# VIC20_HypExp.net
KiCad netlist of a schematic drawn in EAGLE
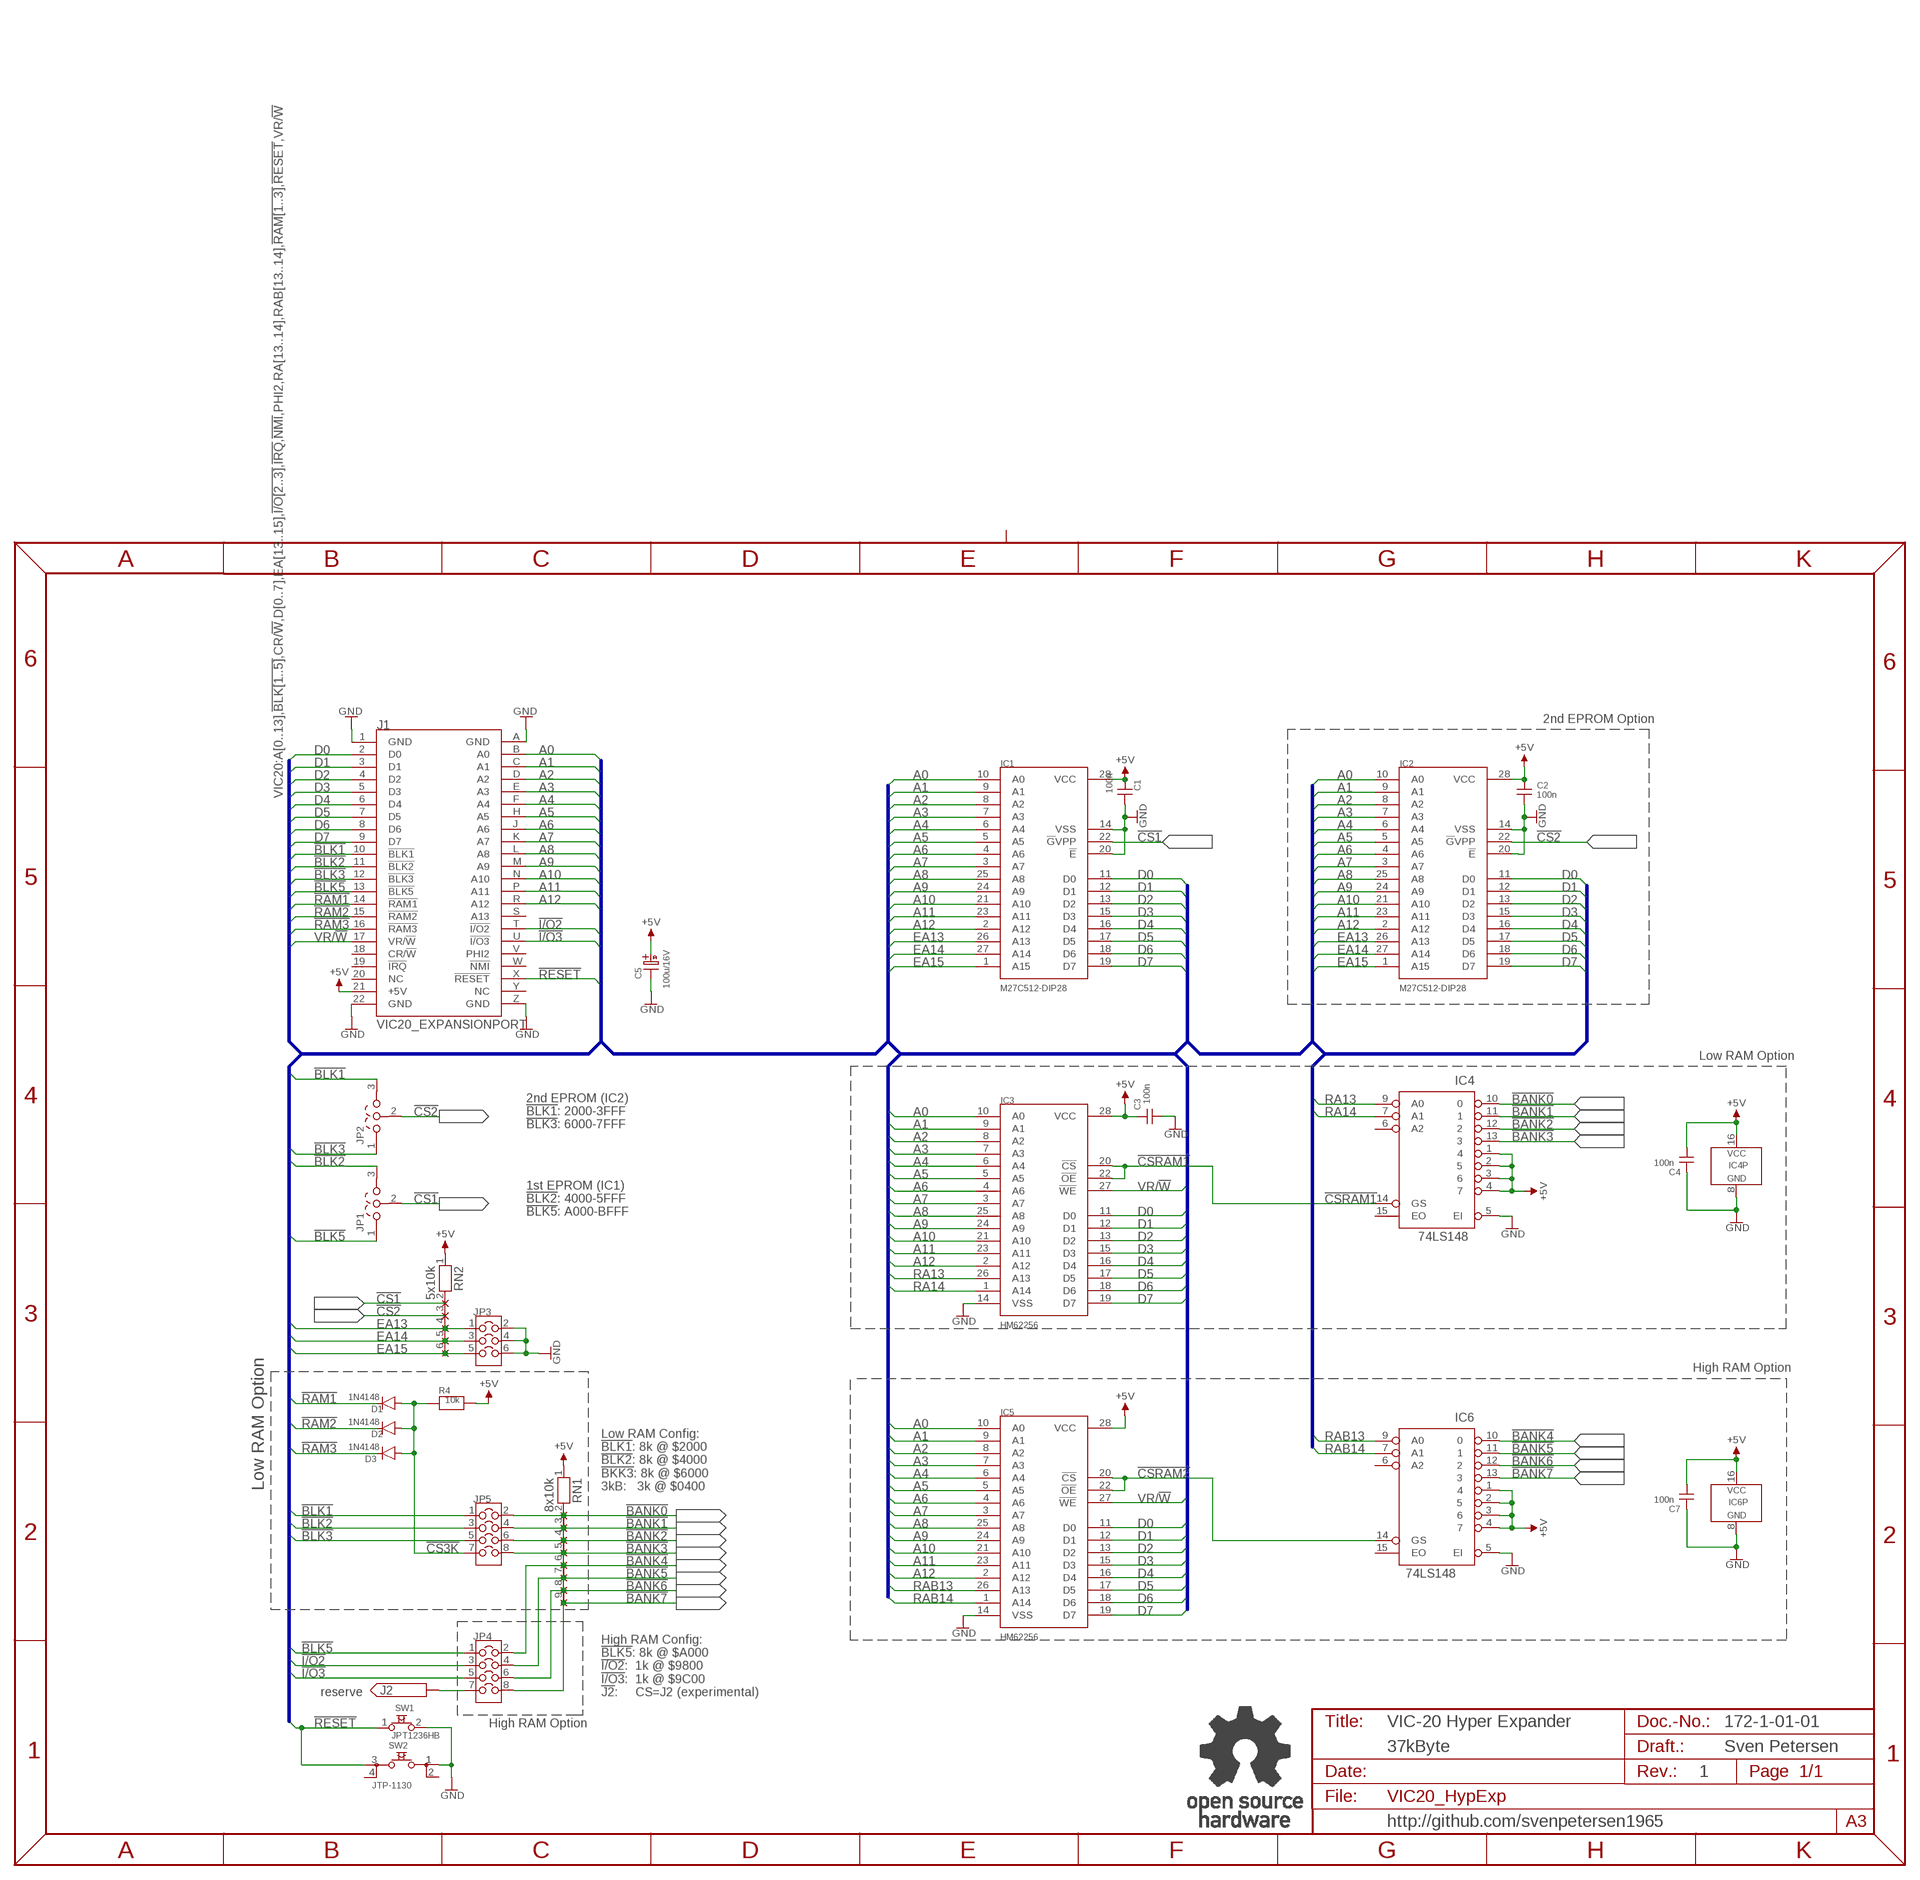
[diagram p0: schematic, sheet 1]

(export (version "E")
  (design (tool "Eeschema 10.0.6"))
  (components
    (comp (ref "C1")
      (value "100n")
      (footprint "eagle-import:C-2,5")
      (libsource (lib "eagle-import") (part "CAP01"))
    )
    (comp (ref "C2")
      (value "100n")
      (footprint "eagle-import:C-2,5")
      (libsource (lib "eagle-import") (part "CAP01"))
    )
    (comp (ref "C3")
      (value "100n")
      (footprint "eagle-import:C-2,5")
      (libsource (lib "eagle-import") (part "CAP01"))
    )
    (comp (ref "C4")
      (value "100n")
      (footprint "eagle-import:C-2,5")
      (libsource (lib "eagle-import") (part "CAP01"))
    )
    (comp (ref "C5")
      (value "100u/16V")
      (footprint "eagle-import:C07_2,5")
      (libsource (lib "eagle-import") (part "C07/2,5"))
    )
    (comp (ref "C7")
      (value "100n")
      (footprint "eagle-import:C-2,5")
      (libsource (lib "eagle-import") (part "CAP01"))
    )
    (comp (ref "D1")
      (value "1N4148")
      (footprint "eagle-import:DO-35_3")
      (libsource (lib "eagle-import") (part "1N41480.3{dblquote}"))
    )
    (comp (ref "D2")
      (value "1N4148")
      (footprint "eagle-import:DO-35_3")
      (libsource (lib "eagle-import") (part "1N41480.3{dblquote}"))
    )
    (comp (ref "D3")
      (value "1N4148")
      (footprint "eagle-import:DO-35_3")
      (libsource (lib "eagle-import") (part "1N41480.3{dblquote}"))
    )
    (comp (ref "IC1")
      (value "M27C512-DIP28")
      (footprint "eagle-import:DIL28-6")
      (libsource (lib "eagle-import") (part "M27C512-DIP28"))
    )
    (comp (ref "IC2")
      (value "M27C512-DIP28")
      (footprint "eagle-import:DIL28-6")
      (libsource (lib "eagle-import") (part "M27C512-DIP28"))
    )
    (comp (ref "IC3")
      (value "HM62256")
      (footprint "eagle-import:DIL28-6")
      (libsource (lib "eagle-import") (part "HM62256"))
    )
    (comp (ref "IC4")
      (value "74LS148")
      (footprint "eagle-import:DIL-16")
      (libsource (lib "eagle-import") (part "74148DIL"))
    )
    (comp (ref "IC5")
      (value "HM62256")
      (footprint "eagle-import:DIL28-6")
      (libsource (lib "eagle-import") (part "HM62256"))
    )
    (comp (ref "IC6")
      (value "74LS148")
      (footprint "eagle-import:DIL-16")
      (libsource (lib "eagle-import") (part "74148DIL"))
    )
    (comp (ref "J1")
      (value "VIC20_EXPANSIONPORT")
      (footprint "eagle-import:VIC20_EXPANSION")
      (libsource (lib "eagle-import") (part "VIC20_EXPANSIONPORT"))
    )
    (comp (ref "J2")
      (value "PINHD-1X1")
      (footprint "eagle-import:1X01")
      (libsource (lib "eagle-import") (part "PINHD-1X1"))
    )
    (comp (ref "JP1")
      (value "COMBI-3P")
      (footprint "eagle-import:COMBI-3P")
      (libsource (lib "eagle-import") (part "COMBI-3P"))
    )
    (comp (ref "JP2")
      (value "COMBI-3P")
      (footprint "eagle-import:COMBI-3P")
      (libsource (lib "eagle-import") (part "COMBI-3P"))
    )
    (comp (ref "JP3")
      (value "COMBI-3X2P")
      (footprint "eagle-import:COMBI-3X2")
      (libsource (lib "eagle-import") (part "COMBI-3X2P"))
    )
    (comp (ref "JP4")
      (value "COMBI-4X2P")
      (footprint "eagle-import:COMBI-4X2")
      (libsource (lib "eagle-import") (part "COMBI-4X2P"))
    )
    (comp (ref "JP5")
      (value "COMBI-4X2P")
      (footprint "eagle-import:COMBI-4X2")
      (libsource (lib "eagle-import") (part "COMBI-4X2P"))
    )
    (comp (ref "R4")
      (value "10k")
      (footprint "eagle-import:R-10")
      (libsource (lib "eagle-import") (part "RES04"))
    )
    (comp (ref "RN1")
      (value "8x10k")
      (footprint "eagle-import:RN-9")
      (libsource (lib "eagle-import") (part "RN08"))
    )
    (comp (ref "RN2")
      (value "5x10k")
      (footprint "eagle-import:RN-6")
      (libsource (lib "eagle-import") (part "RN05"))
    )
    (comp (ref "SW1")
      (value "JPT1236HB")
      (footprint "eagle-import:JTP_1236HB")
      (libsource (lib "eagle-import") (part "JPT1236HB"))
    )
    (comp (ref "SW2")
      (value "JTP-1130")
      (footprint "eagle-import:JTP-1130")
      (libsource (lib "eagle-import") (part "JTP-1130"))
    )
    (comp (ref "U$2")
      (value "OPEN_SOURCE_HW")
      (footprint "eagle-import:OPENHW")
      (libsource (lib "eagle-import") (part "OPEN_SOURCE_HW"))
    )
  )
  (nets
    (net (code "5") (name "+5V") (class "Default")
      (node (ref "C1") (pin "1") (pinfunction "1_1") (pintype "passive"))
      (node (ref "C2") (pin "1") (pinfunction "1_1") (pintype "passive"))
      (node (ref "C3") (pin "2") (pinfunction "2_2") (pintype "passive"))
      (node (ref "C4") (pin "1") (pinfunction "1_1") (pintype "passive"))
      (node (ref "C5") (pin "A") (pinfunction "+_A") (pintype "passive"))
      (node (ref "C7") (pin "1") (pinfunction "1_1") (pintype "passive"))
      (node (ref "IC1") (pin "28") (pinfunction "VCC_28") (pintype "power_in"))
      (node (ref "IC2") (pin "28") (pinfunction "VCC_28") (pintype "power_in"))
      (node (ref "IC3") (pin "28") (pinfunction "VCC_28") (pintype "power_in"))
      (node (ref "IC4") (pin "1") (pinfunction "4_1") (pintype "input"))
      (node (ref "IC4") (pin "16") (pinfunction "VCC_16") (pintype "bidirectional"))
      (node (ref "IC4") (pin "2") (pinfunction "5_2") (pintype "input"))
      (node (ref "IC4") (pin "3") (pinfunction "6_3") (pintype "input"))
      (node (ref "IC4") (pin "4") (pinfunction "7_4") (pintype "input"))
      (node (ref "IC5") (pin "28") (pinfunction "VCC_28") (pintype "power_in"))
      (node (ref "IC6") (pin "1") (pinfunction "4_1") (pintype "input"))
      (node (ref "IC6") (pin "16") (pinfunction "VCC_16") (pintype "bidirectional"))
      (node (ref "IC6") (pin "2") (pinfunction "5_2") (pintype "input"))
      (node (ref "IC6") (pin "3") (pinfunction "6_3") (pintype "input"))
      (node (ref "IC6") (pin "4") (pinfunction "7_4") (pintype "input"))
      (node (ref "J1") (pin "21") (pinfunction "+5V_21") (pintype "power_in"))
      (node (ref "R4") (pin "2") (pinfunction "2_2") (pintype "passive"))
      (node (ref "RN1") (pin "1") (pinfunction "1_1") (pintype "passive"))
      (node (ref "RN2") (pin "1") (pinfunction "1_1") (pintype "passive"))
    )
    (net (code "6") (name "/A0") (class "Default")
      (node (ref "IC1") (pin "10") (pinfunction "A0_10") (pintype "input"))
      (node (ref "IC2") (pin "10") (pinfunction "A0_10") (pintype "input"))
      (node (ref "IC3") (pin "10") (pinfunction "A0_10") (pintype "input"))
      (node (ref "IC5") (pin "10") (pinfunction "A0_10") (pintype "input"))
      (node (ref "J1") (pin "B") (pinfunction "A0_B") (pintype "bidirectional"))
    )
    (net (code "7") (name "/A1") (class "Default")
      (node (ref "IC1") (pin "9") (pinfunction "A1_9") (pintype "input"))
      (node (ref "IC2") (pin "9") (pinfunction "A1_9") (pintype "input"))
      (node (ref "IC3") (pin "9") (pinfunction "A1_9") (pintype "input"))
      (node (ref "IC5") (pin "9") (pinfunction "A1_9") (pintype "input"))
      (node (ref "J1") (pin "C") (pinfunction "A1_C") (pintype "bidirectional"))
    )
    (net (code "8") (name "/A2") (class "Default")
      (node (ref "IC1") (pin "8") (pinfunction "A2_8") (pintype "input"))
      (node (ref "IC2") (pin "8") (pinfunction "A2_8") (pintype "input"))
      (node (ref "IC3") (pin "8") (pinfunction "A2_8") (pintype "input"))
      (node (ref "IC5") (pin "8") (pinfunction "A2_8") (pintype "input"))
      (node (ref "J1") (pin "D") (pinfunction "A2_D") (pintype "bidirectional"))
    )
    (net (code "9") (name "/A3") (class "Default")
      (node (ref "IC1") (pin "7") (pinfunction "A3_7") (pintype "input"))
      (node (ref "IC2") (pin "7") (pinfunction "A3_7") (pintype "input"))
      (node (ref "IC3") (pin "7") (pinfunction "A3_7") (pintype "input"))
      (node (ref "IC5") (pin "7") (pinfunction "A3_7") (pintype "input"))
      (node (ref "J1") (pin "E") (pinfunction "A3_E") (pintype "bidirectional"))
    )
    (net (code "10") (name "/A4") (class "Default")
      (node (ref "IC1") (pin "6") (pinfunction "A4_6") (pintype "input"))
      (node (ref "IC2") (pin "6") (pinfunction "A4_6") (pintype "input"))
      (node (ref "IC3") (pin "6") (pinfunction "A4_6") (pintype "input"))
      (node (ref "IC5") (pin "6") (pinfunction "A4_6") (pintype "input"))
      (node (ref "J1") (pin "F") (pinfunction "A4_F") (pintype "bidirectional"))
    )
    (net (code "11") (name "/A5") (class "Default")
      (node (ref "IC1") (pin "5") (pinfunction "A5_5") (pintype "input"))
      (node (ref "IC2") (pin "5") (pinfunction "A5_5") (pintype "input"))
      (node (ref "IC3") (pin "5") (pinfunction "A5_5") (pintype "input"))
      (node (ref "IC5") (pin "5") (pinfunction "A5_5") (pintype "input"))
      (node (ref "J1") (pin "H") (pinfunction "A5_H") (pintype "bidirectional"))
    )
    (net (code "12") (name "/A6") (class "Default")
      (node (ref "IC1") (pin "4") (pinfunction "A6_4") (pintype "input"))
      (node (ref "IC2") (pin "4") (pinfunction "A6_4") (pintype "input"))
      (node (ref "IC3") (pin "4") (pinfunction "A6_4") (pintype "input"))
      (node (ref "IC5") (pin "4") (pinfunction "A6_4") (pintype "input"))
      (node (ref "J1") (pin "J") (pinfunction "A6_J") (pintype "bidirectional"))
    )
    (net (code "13") (name "/A7") (class "Default")
      (node (ref "IC1") (pin "3") (pinfunction "A7_3") (pintype "input"))
      (node (ref "IC2") (pin "3") (pinfunction "A7_3") (pintype "input"))
      (node (ref "IC3") (pin "3") (pinfunction "A7_3") (pintype "input"))
      (node (ref "IC5") (pin "3") (pinfunction "A7_3") (pintype "input"))
      (node (ref "J1") (pin "K") (pinfunction "A7_K") (pintype "bidirectional"))
    )
    (net (code "14") (name "/A8") (class "Default")
      (node (ref "IC1") (pin "25") (pinfunction "A8_25") (pintype "input"))
      (node (ref "IC2") (pin "25") (pinfunction "A8_25") (pintype "input"))
      (node (ref "IC3") (pin "25") (pinfunction "A8_25") (pintype "input"))
      (node (ref "IC5") (pin "25") (pinfunction "A8_25") (pintype "input"))
      (node (ref "J1") (pin "L") (pinfunction "A8_L") (pintype "bidirectional"))
    )
    (net (code "15") (name "/A9") (class "Default")
      (node (ref "IC1") (pin "24") (pinfunction "A9_24") (pintype "input"))
      (node (ref "IC2") (pin "24") (pinfunction "A9_24") (pintype "input"))
      (node (ref "IC3") (pin "24") (pinfunction "A9_24") (pintype "input"))
      (node (ref "IC5") (pin "24") (pinfunction "A9_24") (pintype "input"))
      (node (ref "J1") (pin "M") (pinfunction "A9_M") (pintype "bidirectional"))
    )
    (net (code "16") (name "/A10") (class "Default")
      (node (ref "IC1") (pin "21") (pinfunction "A10_21") (pintype "input"))
      (node (ref "IC2") (pin "21") (pinfunction "A10_21") (pintype "input"))
      (node (ref "IC3") (pin "21") (pinfunction "A10_21") (pintype "input"))
      (node (ref "IC5") (pin "21") (pinfunction "A10_21") (pintype "input"))
      (node (ref "J1") (pin "N") (pinfunction "A10_N") (pintype "bidirectional"))
    )
    (net (code "17") (name "/A11") (class "Default")
      (node (ref "IC1") (pin "23") (pinfunction "A11_23") (pintype "input"))
      (node (ref "IC2") (pin "23") (pinfunction "A11_23") (pintype "input"))
      (node (ref "IC3") (pin "23") (pinfunction "A11_23") (pintype "input"))
      (node (ref "IC5") (pin "23") (pinfunction "A11_23") (pintype "input"))
      (node (ref "J1") (pin "P") (pinfunction "A11_P") (pintype "bidirectional"))
    )
    (net (code "18") (name "/A12") (class "Default")
      (node (ref "IC1") (pin "2") (pinfunction "A12_2") (pintype "input"))
      (node (ref "IC2") (pin "2") (pinfunction "A12_2") (pintype "input"))
      (node (ref "IC3") (pin "2") (pinfunction "A12_2") (pintype "input"))
      (node (ref "IC5") (pin "2") (pinfunction "A12_2") (pintype "input"))
      (node (ref "J1") (pin "R") (pinfunction "A12_R") (pintype "bidirectional"))
    )
    (net (code "19") (name "/D0") (class "Default")
      (node (ref "IC1") (pin "11") (pinfunction "D0_11") (pintype "bidirectional"))
      (node (ref "IC2") (pin "11") (pinfunction "D0_11") (pintype "bidirectional"))
      (node (ref "IC3") (pin "11") (pinfunction "D0_11") (pintype "bidirectional"))
      (node (ref "IC5") (pin "11") (pinfunction "D0_11") (pintype "bidirectional"))
      (node (ref "J1") (pin "2") (pinfunction "D0_2") (pintype "bidirectional"))
    )
    (net (code "20") (name "/D1") (class "Default")
      (node (ref "IC1") (pin "12") (pinfunction "D1_12") (pintype "bidirectional"))
      (node (ref "IC2") (pin "12") (pinfunction "D1_12") (pintype "bidirectional"))
      (node (ref "IC3") (pin "12") (pinfunction "D1_12") (pintype "bidirectional"))
      (node (ref "IC5") (pin "12") (pinfunction "D1_12") (pintype "bidirectional"))
      (node (ref "J1") (pin "3") (pinfunction "D1_3") (pintype "bidirectional"))
    )
    (net (code "21") (name "/D2") (class "Default")
      (node (ref "IC1") (pin "13") (pinfunction "D2_13") (pintype "bidirectional"))
      (node (ref "IC2") (pin "13") (pinfunction "D2_13") (pintype "bidirectional"))
      (node (ref "IC3") (pin "13") (pinfunction "D2_13") (pintype "bidirectional"))
      (node (ref "IC5") (pin "13") (pinfunction "D2_13") (pintype "bidirectional"))
      (node (ref "J1") (pin "4") (pinfunction "D2_4") (pintype "bidirectional"))
    )
    (net (code "22") (name "/D3") (class "Default")
      (node (ref "IC1") (pin "15") (pinfunction "D3_15") (pintype "bidirectional"))
      (node (ref "IC2") (pin "15") (pinfunction "D3_15") (pintype "bidirectional"))
      (node (ref "IC3") (pin "15") (pinfunction "D3_15") (pintype "bidirectional"))
      (node (ref "IC5") (pin "15") (pinfunction "D3_15") (pintype "bidirectional"))
      (node (ref "J1") (pin "5") (pinfunction "D3_5") (pintype "bidirectional"))
    )
    (net (code "23") (name "/D4") (class "Default")
      (node (ref "IC1") (pin "16") (pinfunction "D4_16") (pintype "bidirectional"))
      (node (ref "IC2") (pin "16") (pinfunction "D4_16") (pintype "bidirectional"))
      (node (ref "IC3") (pin "16") (pinfunction "D4_16") (pintype "bidirectional"))
      (node (ref "IC5") (pin "16") (pinfunction "D4_16") (pintype "bidirectional"))
      (node (ref "J1") (pin "6") (pinfunction "D4_6") (pintype "bidirectional"))
    )
    (net (code "24") (name "/D5") (class "Default")
      (node (ref "IC1") (pin "17") (pinfunction "D5_17") (pintype "bidirectional"))
      (node (ref "IC2") (pin "17") (pinfunction "D5_17") (pintype "bidirectional"))
      (node (ref "IC3") (pin "17") (pinfunction "D5_17") (pintype "bidirectional"))
      (node (ref "IC5") (pin "17") (pinfunction "D5_17") (pintype "bidirectional"))
      (node (ref "J1") (pin "7") (pinfunction "D5_7") (pintype "bidirectional"))
    )
    (net (code "25") (name "/D6") (class "Default")
      (node (ref "IC1") (pin "18") (pinfunction "D6_18") (pintype "bidirectional"))
      (node (ref "IC2") (pin "18") (pinfunction "D6_18") (pintype "bidirectional"))
      (node (ref "IC3") (pin "18") (pinfunction "D6_18") (pintype "bidirectional"))
      (node (ref "IC5") (pin "18") (pinfunction "D6_18") (pintype "bidirectional"))
      (node (ref "J1") (pin "8") (pinfunction "D6_8") (pintype "bidirectional"))
    )
    (net (code "26") (name "/D7") (class "Default")
      (node (ref "IC1") (pin "19") (pinfunction "D7_19") (pintype "bidirectional"))
      (node (ref "IC2") (pin "19") (pinfunction "D7_19") (pintype "bidirectional"))
      (node (ref "IC3") (pin "19") (pinfunction "D7_19") (pintype "bidirectional"))
      (node (ref "IC5") (pin "19") (pinfunction "D7_19") (pintype "bidirectional"))
      (node (ref "J1") (pin "9") (pinfunction "D7_9") (pintype "bidirectional"))
    )
    (net (code "27") (name "/EA13") (class "Default")
      (node (ref "IC1") (pin "26") (pinfunction "A13_26") (pintype "input"))
      (node (ref "IC2") (pin "26") (pinfunction "A13_26") (pintype "input"))
      (node (ref "JP3") (pin "1") (pinfunction "1_1") (pintype "bidirectional"))
      (node (ref "RN2") (pin "4") (pinfunction "4_4") (pintype "passive"))
    )
    (net (code "28") (name "/EA14") (class "Default")
      (node (ref "IC1") (pin "27") (pinfunction "A14_27") (pintype "input"))
      (node (ref "IC2") (pin "27") (pinfunction "A14_27") (pintype "input"))
      (node (ref "JP3") (pin "3") (pinfunction "3_3") (pintype "bidirectional"))
      (node (ref "RN2") (pin "5") (pinfunction "5_5") (pintype "passive"))
    )
    (net (code "29") (name "/EA15") (class "Default")
      (node (ref "IC1") (pin "1") (pinfunction "A15_1") (pintype "input"))
      (node (ref "IC2") (pin "1") (pinfunction "A15_1") (pintype "input"))
      (node (ref "JP3") (pin "5") (pinfunction "5_5") (pintype "bidirectional"))
      (node (ref "RN2") (pin "6") (pinfunction "6_6") (pintype "passive"))
    )
    (net (code "30") (name "/NC") (class "Default")
      (node (ref "J1") (pin "20") (pinfunction "NC_20") (pintype "power_in"))
    )
    (net (code "31") (name "/RA13") (class "Default")
      (node (ref "IC3") (pin "26") (pinfunction "A13_26") (pintype "input"))
      (node (ref "IC4") (pin "9") (pinfunction "A0_9") (pintype "output"))
    )
    (net (code "32") (name "/RA14") (class "Default")
      (node (ref "IC3") (pin "1") (pinfunction "A14_1") (pintype "input"))
      (node (ref "IC4") (pin "7") (pinfunction "A1_7") (pintype "output"))
    )
    (net (code "33") (name "/RAB13") (class "Default")
      (node (ref "IC5") (pin "26") (pinfunction "A13_26") (pintype "input"))
      (node (ref "IC6") (pin "9") (pinfunction "A0_9") (pintype "output"))
    )
    (net (code "34") (name "/RAB14") (class "Default")
      (node (ref "IC5") (pin "1") (pinfunction "A14_1") (pintype "input"))
      (node (ref "IC6") (pin "7") (pinfunction "A1_7") (pintype "output"))
    )
    (net (code "35") (name "/VR{slash}~{W}") (class "Default")
      (node (ref "IC3") (pin "27") (pinfunction "~{WE}_27") (pintype "input"))
      (node (ref "IC5") (pin "27") (pinfunction "~{WE}_27") (pintype "input"))
      (node (ref "J1") (pin "17") (pinfunction "VR/~{W}_17") (pintype "output"))
    )
    (net (code "37") (name "/~{BANK0}") (class "Default")
      (node (ref "IC4") (pin "10") (pinfunction "0_10") (pintype "input"))
      (node (ref "JP5") (pin "2") (pinfunction "2_2") (pintype "bidirectional"))
      (node (ref "RN1") (pin "2") (pinfunction "2_2") (pintype "passive"))
    )
    (net (code "38") (name "/~{BANK1}") (class "Default")
      (node (ref "IC4") (pin "11") (pinfunction "1_11") (pintype "input"))
      (node (ref "JP5") (pin "4") (pinfunction "4_4") (pintype "bidirectional"))
      (node (ref "RN1") (pin "3") (pinfunction "3_3") (pintype "passive"))
    )
    (net (code "39") (name "/~{BANK2}") (class "Default")
      (node (ref "IC4") (pin "12") (pinfunction "2_12") (pintype "input"))
      (node (ref "JP5") (pin "6") (pinfunction "6_6") (pintype "bidirectional"))
      (node (ref "RN1") (pin "4") (pinfunction "4_4") (pintype "passive"))
    )
    (net (code "40") (name "/~{BANK3}") (class "Default")
      (node (ref "IC4") (pin "13") (pinfunction "3_13") (pintype "input"))
      (node (ref "JP5") (pin "8") (pinfunction "8_8") (pintype "bidirectional"))
      (node (ref "RN1") (pin "5") (pinfunction "5_5") (pintype "passive"))
    )
    (net (code "41") (name "/~{BANK4}") (class "Default")
      (node (ref "IC6") (pin "10") (pinfunction "0_10") (pintype "input"))
      (node (ref "JP4") (pin "2") (pinfunction "2_2") (pintype "bidirectional"))
      (node (ref "RN1") (pin "6") (pinfunction "6_6") (pintype "passive"))
    )
    (net (code "42") (name "/~{BANK5}") (class "Default")
      (node (ref "IC6") (pin "11") (pinfunction "1_11") (pintype "input"))
      (node (ref "JP4") (pin "4") (pinfunction "4_4") (pintype "bidirectional"))
      (node (ref "RN1") (pin "7") (pinfunction "7_7") (pintype "passive"))
    )
    (net (code "43") (name "/~{BANK6}") (class "Default")
      (node (ref "IC6") (pin "12") (pinfunction "2_12") (pintype "input"))
      (node (ref "JP4") (pin "6") (pinfunction "6_6") (pintype "bidirectional"))
      (node (ref "RN1") (pin "8") (pinfunction "8_8") (pintype "passive"))
    )
    (net (code "44") (name "/~{BANK7}") (class "Default")
      (node (ref "IC6") (pin "13") (pinfunction "3_13") (pintype "input"))
      (node (ref "JP4") (pin "8") (pinfunction "8_8") (pintype "bidirectional"))
      (node (ref "RN1") (pin "9") (pinfunction "9_9") (pintype "passive"))
    )
    (net (code "45") (name "/~{BLK1}") (class "Default")
      (node (ref "J1") (pin "10") (pinfunction "~{BLK1}_10") (pintype "input"))
      (node (ref "JP2") (pin "3") (pinfunction "3_3") (pintype "bidirectional"))
      (node (ref "JP5") (pin "1") (pinfunction "1_1") (pintype "bidirectional"))
    )
    (net (code "46") (name "/~{BLK2}") (class "Default")
      (node (ref "J1") (pin "11") (pinfunction "~{BLK2}_11") (pintype "input"))
      (node (ref "JP1") (pin "3") (pinfunction "3_3") (pintype "bidirectional"))
      (node (ref "JP5") (pin "3") (pinfunction "3_3") (pintype "bidirectional"))
    )
    (net (code "47") (name "/~{BLK3}") (class "Default")
      (node (ref "J1") (pin "12") (pinfunction "~{BLK3}_12") (pintype "output"))
      (node (ref "JP2") (pin "1") (pinfunction "1_1") (pintype "bidirectional"))
      (node (ref "JP5") (pin "5") (pinfunction "5_5") (pintype "bidirectional"))
    )
    (net (code "48") (name "/~{BLK5}") (class "Default")
      (node (ref "J1") (pin "13") (pinfunction "~{BLK5}_13") (pintype "output"))
      (node (ref "JP1") (pin "1") (pinfunction "1_1") (pintype "bidirectional"))
      (node (ref "JP4") (pin "1") (pinfunction "1_1") (pintype "bidirectional"))
    )
    (net (code "49") (name "/~{CS1}") (class "Default")
      (node (ref "IC1") (pin "22") (pinfunction "~{G}VPP_22") (pintype "input"))
      (node (ref "JP1") (pin "2") (pinfunction "2_2") (pintype "bidirectional"))
      (node (ref "RN2") (pin "2") (pinfunction "2_2") (pintype "passive"))
    )
    (net (code "50") (name "/~{CS2}") (class "Default")
      (node (ref "IC2") (pin "22") (pinfunction "~{G}VPP_22") (pintype "input"))
      (node (ref "JP2") (pin "2") (pinfunction "2_2") (pintype "bidirectional"))
      (node (ref "RN2") (pin "3") (pinfunction "3_3") (pintype "passive"))
    )
    (net (code "51") (name "/~{CS3K}") (class "Default")
      (node (ref "D1") (pin "A") (pinfunction "A_A") (pintype "passive"))
      (node (ref "D2") (pin "A") (pinfunction "A_A") (pintype "passive"))
      (node (ref "D3") (pin "A") (pinfunction "A_A") (pintype "passive"))
      (node (ref "JP5") (pin "7") (pinfunction "7_7") (pintype "bidirectional"))
      (node (ref "R4") (pin "1") (pinfunction "1_1") (pintype "passive"))
    )
    (net (code "52") (name "/~{CSRAM1}") (class "Default")
      (node (ref "IC3") (pin "20") (pinfunction "~{CS}_20") (pintype "input"))
      (node (ref "IC3") (pin "22") (pinfunction "~{OE}_22") (pintype "input"))
      (node (ref "IC4") (pin "14") (pinfunction "GS_14") (pintype "output"))
    )
    (net (code "53") (name "/~{CSRAM2}") (class "Default")
      (node (ref "IC5") (pin "20") (pinfunction "~{CS}_20") (pintype "input"))
      (node (ref "IC5") (pin "22") (pinfunction "~{OE}_22") (pintype "input"))
      (node (ref "IC6") (pin "14") (pinfunction "GS_14") (pintype "output"))
    )
    (net (code "54") (name "/~{I{slash}O2}") (class "Default")
      (node (ref "J1") (pin "T") (pinfunction "~{I/O2}_T") (pintype "output"))
      (node (ref "JP4") (pin "3") (pinfunction "3_3") (pintype "bidirectional"))
    )
    (net (code "55") (name "/~{I{slash}O3}") (class "Default")
      (node (ref "J1") (pin "U") (pinfunction "~{I/O3}_U") (pintype "output"))
      (node (ref "JP4") (pin "5") (pinfunction "5_5") (pintype "bidirectional"))
    )
    (net (code "56") (name "/~{RAM1}") (class "Default")
      (node (ref "D1") (pin "K") (pinfunction "K_K") (pintype "passive"))
      (node (ref "J1") (pin "14") (pinfunction "~{RAM1}_14") (pintype "input"))
    )
    (net (code "57") (name "/~{RAM2}") (class "Default")
      (node (ref "D2") (pin "K") (pinfunction "K_K") (pintype "passive"))
      (node (ref "J1") (pin "15") (pinfunction "~{RAM2}_15") (pintype "output"))
    )
    (net (code "58") (name "/~{RAM3}") (class "Default")
      (node (ref "D3") (pin "K") (pinfunction "K_K") (pintype "passive"))
      (node (ref "J1") (pin "16") (pinfunction "~{RAM3}_16") (pintype "output"))
    )
    (net (code "59") (name "/~{RESET}") (class "Default")
      (node (ref "J1") (pin "X") (pinfunction "~{RESET}_X") (pintype "open_collector"))
      (node (ref "SW1") (pin "1") (pinfunction "1_1") (pintype "passive"))
      (node (ref "SW2") (pin "3") (pinfunction "3_3") (pintype "passive"))
    )
    (net (code "60") (name "GND") (class "Default")
      (node (ref "C1") (pin "2") (pinfunction "2_2") (pintype "passive"))
      (node (ref "C2") (pin "2") (pinfunction "2_2") (pintype "passive"))
      (node (ref "C3") (pin "1") (pinfunction "1_1") (pintype "passive"))
      (node (ref "C4") (pin "2") (pinfunction "2_2") (pintype "passive"))
      (node (ref "C5") (pin "K") (pinfunction "-_K") (pintype "passive"))
      (node (ref "C7") (pin "2") (pinfunction "2_2") (pintype "passive"))
      (node (ref "IC1") (pin "14") (pinfunction "VSS_14") (pintype "power_in"))
      (node (ref "IC1") (pin "20") (pinfunction "~{E}_20") (pintype "input"))
      (node (ref "IC2") (pin "14") (pinfunction "VSS_14") (pintype "power_in"))
      (node (ref "IC2") (pin "20") (pinfunction "~{E}_20") (pintype "input"))
      (node (ref "IC3") (pin "14") (pinfunction "VSS_14") (pintype "power_in"))
      (node (ref "IC4") (pin "5") (pinfunction "EI_5") (pintype "input"))
      (node (ref "IC4") (pin "8") (pinfunction "GND_8") (pintype "bidirectional"))
      (node (ref "IC5") (pin "14") (pinfunction "VSS_14") (pintype "power_in"))
      (node (ref "IC6") (pin "5") (pinfunction "EI_5") (pintype "input"))
      (node (ref "IC6") (pin "8") (pinfunction "GND_8") (pintype "bidirectional"))
      (node (ref "J1") (pin "1") (pinfunction "GND_1") (pintype "power_in"))
      (node (ref "J1") (pin "22") (pinfunction "GND_22") (pintype "power_in"))
      (node (ref "J1") (pin "A") (pinfunction "GND_A") (pintype "power_in"))
      (node (ref "J1") (pin "Z") (pinfunction "GND_Z") (pintype "power_in"))
      (node (ref "JP3") (pin "2") (pinfunction "2_2") (pintype "bidirectional"))
      (node (ref "JP3") (pin "4") (pinfunction "4_4") (pintype "bidirectional"))
      (node (ref "JP3") (pin "6") (pinfunction "6_6") (pintype "bidirectional"))
      (node (ref "SW1") (pin "2") (pinfunction "2_2") (pintype "passive"))
      (node (ref "SW2") (pin "1") (pinfunction "1_1") (pintype "passive"))
    )
    (net (code "61") (name "Net-(J2-Pad1)") (class "Default")
      (node (ref "J2") (pin "1") (pinfunction "1_1") (pintype "passive"))
      (node (ref "JP4") (pin "7") (pinfunction "7_7") (pintype "bidirectional"))
    )
    (net (code "62") (name "unconnected-(IC4A-A2-Pad6)") (class "Default")
      (node (ref "IC4") (pin "6") (pinfunction "A2_6") (pintype "output"))
    )
    (net (code "63") (name "unconnected-(IC4A-EO-Pad15)") (class "Default")
      (node (ref "IC4") (pin "15") (pinfunction "EO_15") (pintype "output"))
    )
    (net (code "64") (name "unconnected-(IC6A-A2-Pad6)") (class "Default")
      (node (ref "IC6") (pin "6") (pinfunction "A2_6") (pintype "output"))
    )
    (net (code "65") (name "unconnected-(IC6A-EO-Pad15)") (class "Default")
      (node (ref "IC6") (pin "15") (pinfunction "EO_15") (pintype "output"))
    )
    (net (code "66") (name "unconnected-(J1-A13-PadS)") (class "Default")
      (node (ref "J1") (pin "S") (pinfunction "A13_S") (pintype "bidirectional"))
    )
    (net (code "67") (name "unconnected-(J1-CR{slash}~{W}-Pad18)") (class "Default")
      (node (ref "J1") (pin "18") (pinfunction "CR/~{W}_18") (pintype "output"))
    )
    (net (code "68") (name "unconnected-(J1-NC-PadY)") (class "Default")
      (node (ref "J1") (pin "Y") (pinfunction "NC_Y") (pintype "bidirectional"))
    )
    (net (code "69") (name "unconnected-(J1-PHI2-PadV)") (class "Default")
      (node (ref "J1") (pin "V") (pinfunction "PHI2_V") (pintype "bidirectional"))
    )
    (net (code "70") (name "unconnected-(J1-~{IRQ}-Pad19)") (class "Default")
      (node (ref "J1") (pin "19") (pinfunction "~{IRQ}_19") (pintype "input"))
    )
    (net (code "71") (name "unconnected-(J1-~{NMI}-PadW)") (class "Default")
      (node (ref "J1") (pin "W") (pinfunction "~{NMI}_W") (pintype "input"))
    )
    (net (code "72") (name "unconnected-(SW2-Pad2)") (class "Default")
      (node (ref "SW2") (pin "2") (pinfunction "2_2") (pintype "passive"))
    )
    (net (code "73") (name "unconnected-(SW2-Pad4)") (class "Default")
      (node (ref "SW2") (pin "4") (pinfunction "4_4") (pintype "passive"))
    )
  )
)
